# ProPrj__2_2025-03-13.net
KiCad netlist of a schematic drawn in EasyEDA Pro
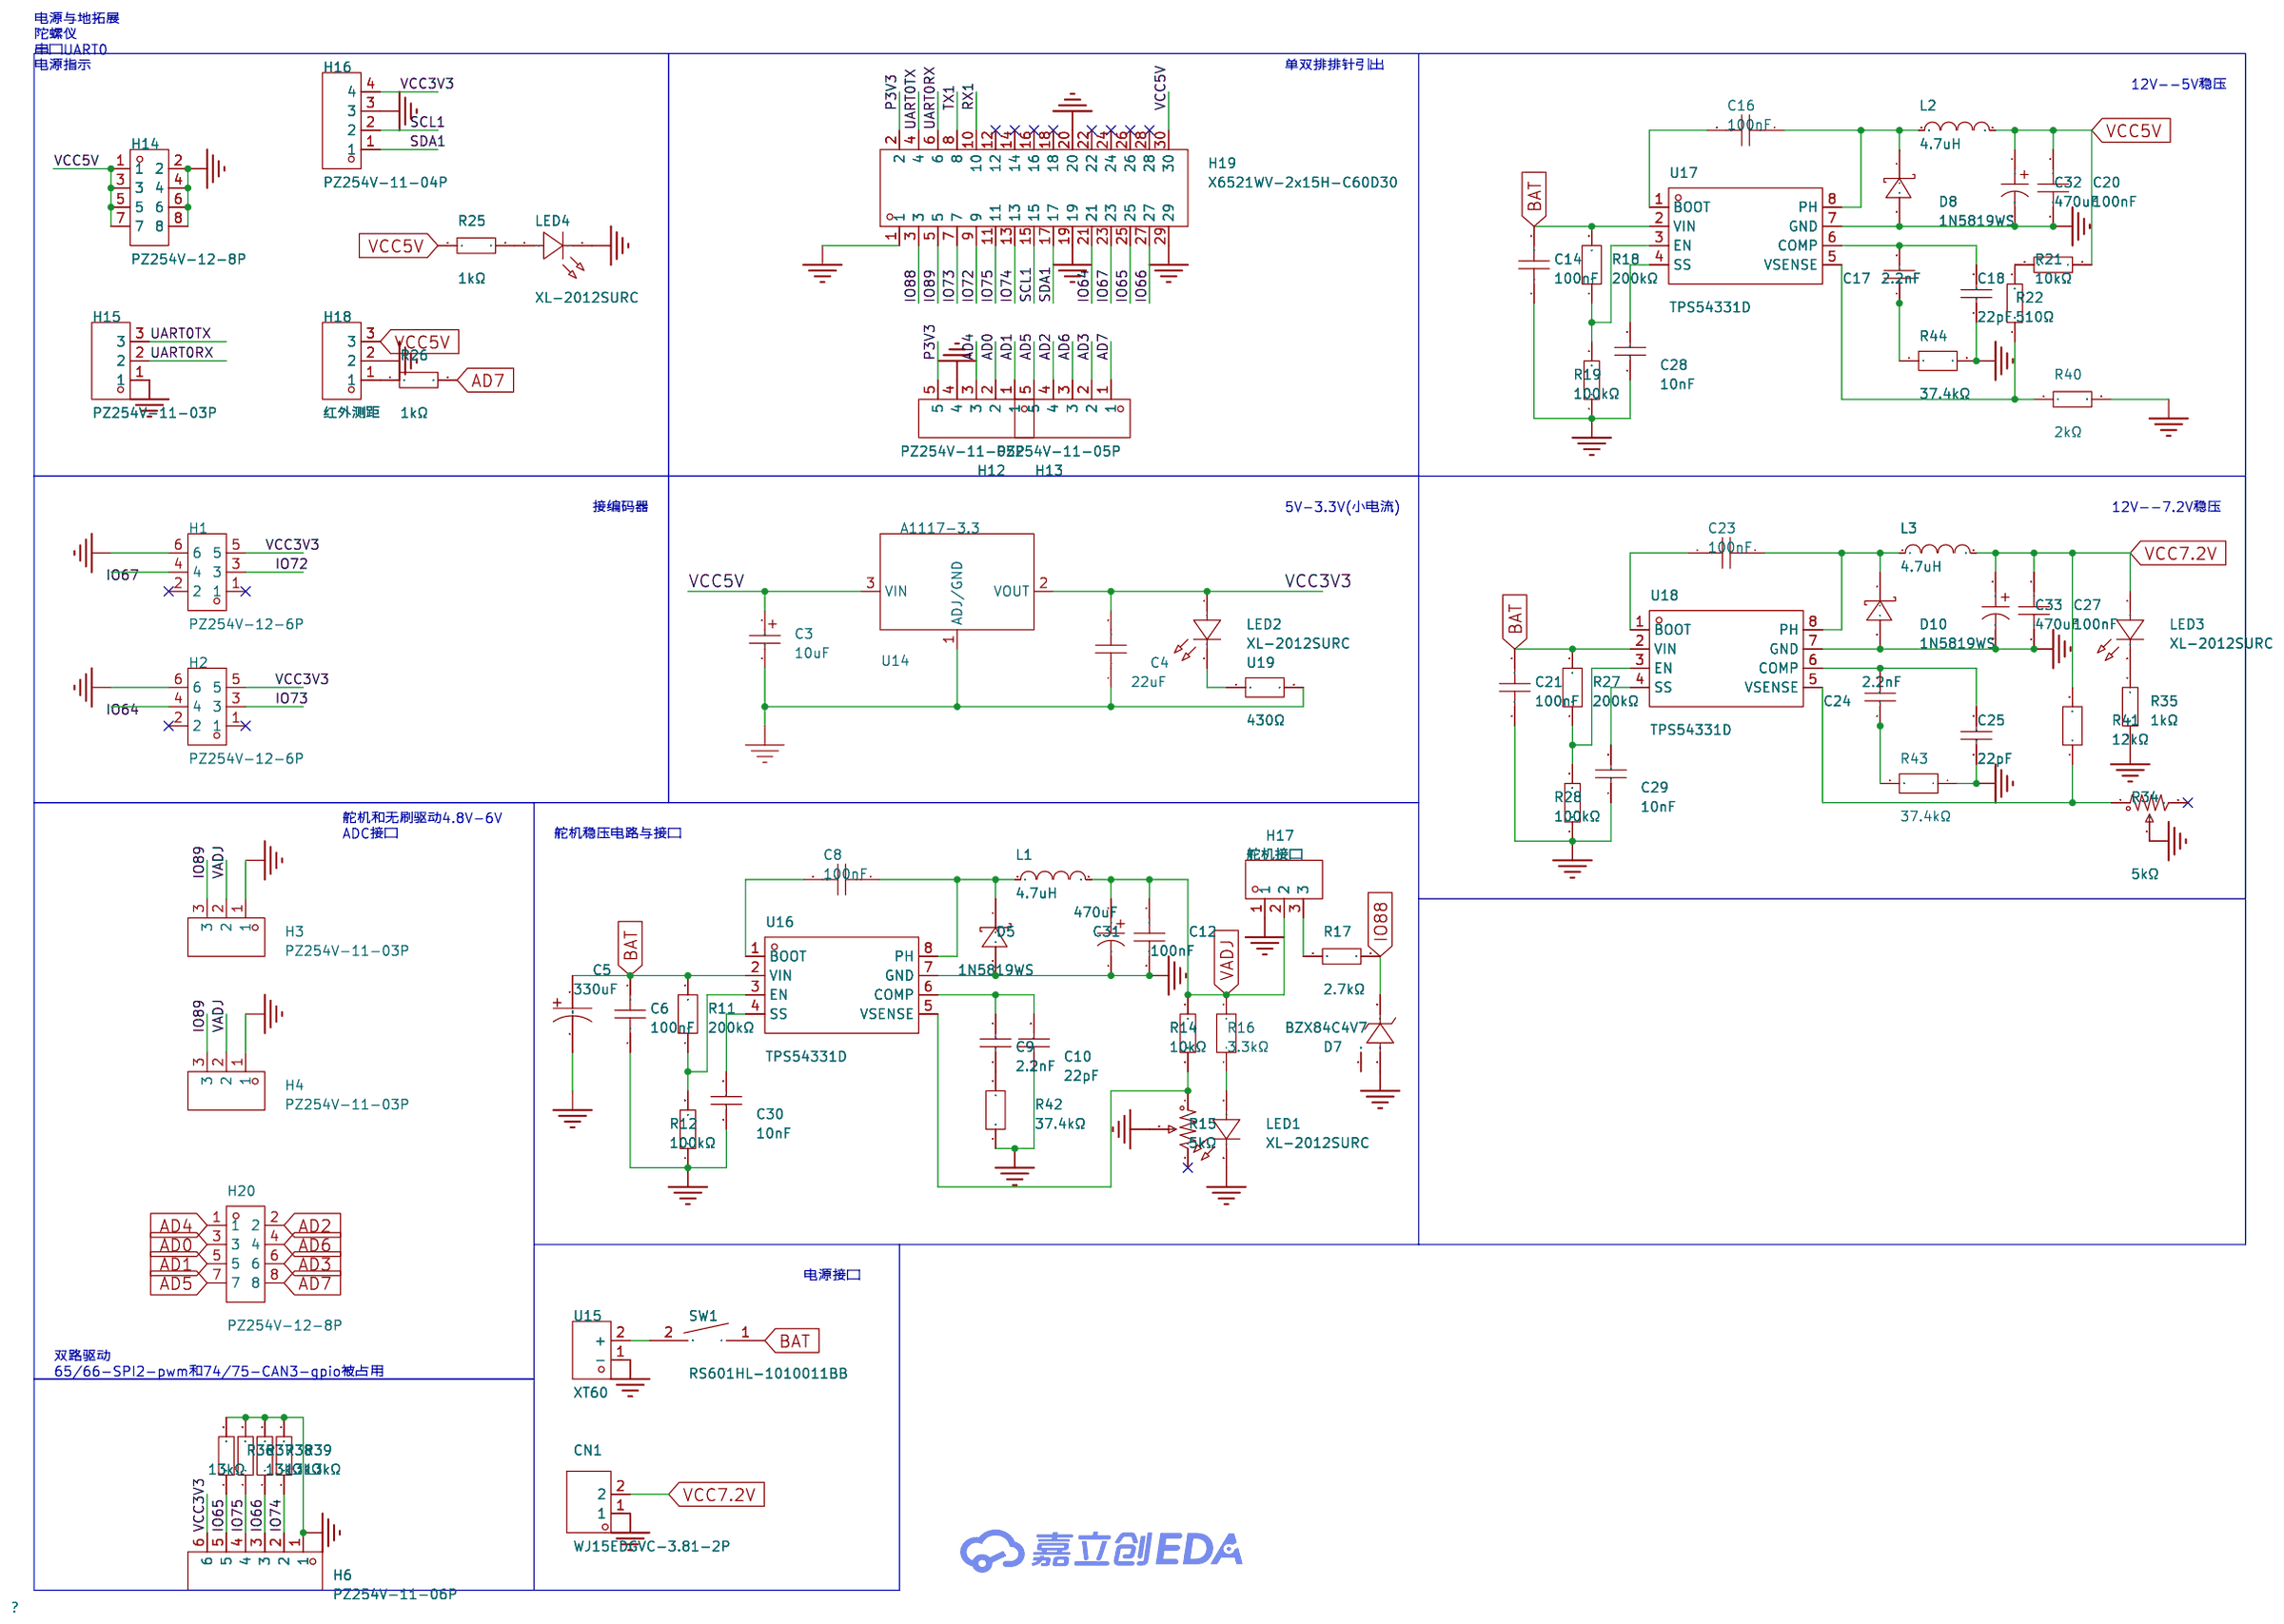
[diagram p0: schematic sheet]

(export (version "E")
  (design (tool "Eeschema 10.0.6"))
  (components
    (comp (ref "C3")
      (value "10uF")
      (footprint "easyedapro:CAP-SMD_L6.0-W3.2")
      (description "容值:10uF;精度:±10%;额定电压:16V;等效串联电阻:2Ω@100kHz;")
      (fields (field (name "Manufacturer Part") "TAJC106K016RNJ") (field (name "Manufacturer") "Kyocera AVX"))
      (libsource (lib "easyedapro") (part "TAJC106K016RNJ"))
    )
    (comp (ref "C4")
      (value "22uF")
      (footprint "easyedapro:C0805")
      (description "容值:22uF;精度:±20%;额定电压:35V;材质(温度系数):X5R;")
      (fields
        (field (name "Manufacturer Part") "CGA0805X5R226M350MT")
        (field (name "Manufacturer") "HRE(芯声)")
      )
      (libsource (lib "easyedapro") (part "CGA0805X5R226M350MT"))
    )
    (comp (ref "C5")
      (value "330uF")
      (footprint "easyedapro:CAP-SMD_BD8.0-L8.3-W8.3-LS9.3-FD-1")
      (description "容值:330uF;精度:±20%;额定电压:25V;纹波电流:228mA@120Hz;等效串联电阻(ESR):-;")
      (fields (field (name "Manufacturer Part") "RVT1E331M0810") (field (name "Manufacturer") "ROQANG(容强)"))
      (libsource (lib "easyedapro") (part "RVT1E331M0810_C335985"))
    )
    (comp (ref "C6")
      (value "100nF")
      (footprint "easyedapro:C0805")
      (description "容值:100nF;精度:±10%;额定电压:50V;材质(温度系数):X7R;")
      (fields
        (field (name "Manufacturer Part") "CC0805KRX7R9BB104")
        (field (name "Manufacturer") "YAGEO(国巨)")
      )
      (libsource (lib "easyedapro") (part "CC0805KRX7R9BB104"))
    )
    (comp (ref "C8")
      (value "100nF")
      (footprint "easyedapro:C0805")
      (description "容值:100nF;精度:±10%;额定电压:50V;材质(温度系数):X7R;")
      (fields
        (field (name "Manufacturer Part") "CC0805KRX7R9BB104")
        (field (name "Manufacturer") "YAGEO(国巨)")
      )
      (libsource (lib "easyedapro") (part "CC0805KRX7R9BB104"))
    )
    (comp (ref "C9")
      (value "2.2nF")
      (footprint "easyedapro:C0805")
      (description "容值:2.2nF;精度:±5%;额定电压:50V;材质(温度系数):C0G;")
      (fields
        (field (name "Manufacturer Part") "CL21C222JBFNNNE")
        (field (name "Manufacturer") "SAMSUNG(三星)")
      )
      (libsource (lib "easyedapro") (part "CL21C222JBFNNNE"))
    )
    (comp (ref "C10")
      (value "22pF")
      (footprint "easyedapro:C0603")
      (description "容值:22pF;精度:±5%;额定电压:50V;材质(温度系数):NP0;")
      (fields
        (field (name "Manufacturer Part") "CC0603JRNPO9BN220")
        (field (name "Manufacturer") "YAGEO(国巨)")
      )
      (libsource (lib "easyedapro") (part "CC0603JRNPO9BN220"))
    )
    (comp (ref "C12")
      (value "100nF")
      (footprint "easyedapro:C0805")
      (description "容值:100nF;精度:±10%;额定电压:50V;材质(温度系数):X7R;")
      (fields
        (field (name "Manufacturer Part") "CC0805KRX7R9BB104")
        (field (name "Manufacturer") "YAGEO(国巨)")
      )
      (libsource (lib "easyedapro") (part "CC0805KRX7R9BB104"))
    )
    (comp (ref "C14")
      (value "100nF")
      (footprint "easyedapro:C0805")
      (description "容值:100nF;精度:±10%;额定电压:50V;材质(温度系数):X7R;")
      (fields
        (field (name "Manufacturer Part") "CC0805KRX7R9BB104")
        (field (name "Manufacturer") "YAGEO(国巨)")
      )
      (libsource (lib "easyedapro") (part "CC0805KRX7R9BB104"))
    )
    (comp (ref "C16")
      (value "100nF")
      (footprint "easyedapro:C0805")
      (description "容值:100nF;精度:±10%;额定电压:50V;材质(温度系数):X7R;")
      (fields
        (field (name "Manufacturer Part") "CC0805KRX7R9BB104")
        (field (name "Manufacturer") "YAGEO(国巨)")
      )
      (libsource (lib "easyedapro") (part "CC0805KRX7R9BB104"))
    )
    (comp (ref "C17")
      (value "2.2nF")
      (footprint "easyedapro:C0805")
      (description "容值:2.2nF;精度:±5%;额定电压:50V;材质(温度系数):C0G;")
      (fields
        (field (name "Manufacturer Part") "CL21C222JBFNNNE")
        (field (name "Manufacturer") "SAMSUNG(三星)")
      )
      (libsource (lib "easyedapro") (part "CL21C222JBFNNNE"))
    )
    (comp (ref "C18")
      (value "22pF")
      (footprint "easyedapro:C0603")
      (description "容值:22pF;精度:±5%;额定电压:50V;材质(温度系数):NP0;")
      (fields
        (field (name "Manufacturer Part") "CC0603JRNPO9BN220")
        (field (name "Manufacturer") "YAGEO(国巨)")
      )
      (libsource (lib "easyedapro") (part "CC0603JRNPO9BN220"))
    )
    (comp (ref "C20")
      (value "100nF")
      (footprint "easyedapro:C0805")
      (description "容值:100nF;精度:±10%;额定电压:50V;材质(温度系数):X7R;")
      (fields
        (field (name "Manufacturer Part") "CC0805KRX7R9BB104")
        (field (name "Manufacturer") "YAGEO(国巨)")
      )
      (libsource (lib "easyedapro") (part "CC0805KRX7R9BB104"))
    )
    (comp (ref "C21")
      (value "100nF")
      (footprint "easyedapro:C0805")
      (description "容值:100nF;精度:±10%;额定电压:50V;材质(温度系数):X7R;")
      (fields
        (field (name "Manufacturer Part") "CC0805KRX7R9BB104")
        (field (name "Manufacturer") "YAGEO(国巨)")
      )
      (libsource (lib "easyedapro") (part "CC0805KRX7R9BB104"))
    )
    (comp (ref "C23")
      (value "100nF")
      (footprint "easyedapro:C0805")
      (description "容值:100nF;精度:±10%;额定电压:50V;材质(温度系数):X7R;")
      (fields
        (field (name "Manufacturer Part") "CC0805KRX7R9BB104")
        (field (name "Manufacturer") "YAGEO(国巨)")
      )
      (libsource (lib "easyedapro") (part "CC0805KRX7R9BB104"))
    )
    (comp (ref "C24")
      (value "2.2nF")
      (footprint "easyedapro:C0805")
      (description "容值:2.2nF;精度:±5%;额定电压:50V;材质(温度系数):C0G;")
      (fields
        (field (name "Manufacturer Part") "CL21C222JBFNNNE")
        (field (name "Manufacturer") "SAMSUNG(三星)")
      )
      (libsource (lib "easyedapro") (part "CL21C222JBFNNNE"))
    )
    (comp (ref "C25")
      (value "22pF")
      (footprint "easyedapro:C0603")
      (description "容值:22pF;精度:±5%;额定电压:50V;材质(温度系数):NP0;")
      (fields
        (field (name "Manufacturer Part") "CC0603JRNPO9BN220")
        (field (name "Manufacturer") "YAGEO(国巨)")
      )
      (libsource (lib "easyedapro") (part "CC0603JRNPO9BN220"))
    )
    (comp (ref "C27")
      (value "100nF")
      (footprint "easyedapro:C0805")
      (description "容值:100nF;精度:±10%;额定电压:50V;材质(温度系数):X7R;")
      (fields
        (field (name "Manufacturer Part") "CC0805KRX7R9BB104")
        (field (name "Manufacturer") "YAGEO(国巨)")
      )
      (libsource (lib "easyedapro") (part "CC0805KRX7R9BB104"))
    )
    (comp (ref "C28")
      (value "10nF")
      (footprint "easyedapro:C0805")
      (description "容值:10nF;精度:±10%;额定电压:50V;材质(温度系数):X7R;")
      (fields
        (field (name "Manufacturer Part") "CL21B103KBANNNC")
        (field (name "Manufacturer") "SAMSUNG(三星)")
      )
      (libsource (lib "easyedapro") (part "CL21B103KBANNNC"))
    )
    (comp (ref "C29")
      (value "10nF")
      (footprint "easyedapro:C0805")
      (description "容值:10nF;精度:±10%;额定电压:50V;材质(温度系数):X7R;")
      (fields
        (field (name "Manufacturer Part") "CL21B103KBANNNC")
        (field (name "Manufacturer") "SAMSUNG(三星)")
      )
      (libsource (lib "easyedapro") (part "CL21B103KBANNNC"))
    )
    (comp (ref "C30")
      (value "10nF")
      (footprint "easyedapro:C0805")
      (description "容值:10nF;精度:±10%;额定电压:50V;材质(温度系数):X7R;")
      (fields
        (field (name "Manufacturer Part") "CL21B103KBANNNC")
        (field (name "Manufacturer") "SAMSUNG(三星)")
      )
      (libsource (lib "easyedapro") (part "CL21B103KBANNNC"))
    )
    (comp (ref "C31")
      (value "470uF")
      (footprint "easyedapro:CAP-SMD_BD8.0-L8.3-W8.3-LS8.9-FD")
      (description "容值:470uF;精度:±20%;额定电压:16V;纹波电流:240mA@120Hz;")
      (fields (field (name "Manufacturer Part") "CK1C471M-CRF10") (field (name "Manufacturer") "ROQANG(容强)"))
      (libsource (lib "easyedapro") (part "CK1C471M-CRF10_C5162359"))
    )
    (comp (ref "C32")
      (value "470uF")
      (footprint "easyedapro:CAP-SMD_BD8.0-L8.3-W8.3-LS8.9-FD")
      (description "容值:470uF;精度:±20%;额定电压:16V;纹波电流:240mA@120Hz;")
      (fields (field (name "Manufacturer Part") "CK1C471M-CRF10") (field (name "Manufacturer") "ROQANG(容强)"))
      (libsource (lib "easyedapro") (part "CK1C471M-CRF10_C5162359"))
    )
    (comp (ref "C33")
      (value "470uF")
      (footprint "easyedapro:CAP-SMD_BD8.0-L8.3-W8.3-LS8.9-FD")
      (description "容值:470uF;精度:±20%;额定电压:16V;纹波电流:240mA@120Hz;")
      (fields (field (name "Manufacturer Part") "CK1C471M-CRF10") (field (name "Manufacturer") "ROQANG(容强)"))
      (libsource (lib "easyedapro") (part "CK1C471M-CRF10_C5162359"))
    )
    (comp (ref "CN1")
      (value "WJ15EDGVC-3.81-2P")
      (footprint "easyedapro:CONN-TH_WJ15EDGVC-3.81-2P")
      (fields (field (name "Manufacturer") "KANGNEX(康奈克斯电气)"))
      (libsource (lib "easyedapro") (part "WJ15EDGVC-3.81-2P"))
    )
    (comp (ref "D5")
      (value "1N5819WS")
      (footprint "easyedapro:SOD-323_L1.8-W1.3-LS2.5-RD")
      (description "正向压降(Vf):600mV@1A;直流反向耐压(Vr):40V;整流电流:1A;")
      (fields (field (name "Manufacturer") "Hottech(合科泰)"))
      (libsource (lib "easyedapro") (part "1N5819WS"))
    )
    (comp (ref "D7")
      (value "BZX84C4V7")
      (footprint "easyedapro:SOT-23-3_L2.9-W1.3-P1.90-LS2.4-BR")
      (description "二极管配置:独立式;稳压值(标称值):4.7V;稳压值(范围):4.4V~5V;耗散功率(Pd):350mW;")
      (fields (field (name "Manufacturer") "LGE(鲁光)"))
      (libsource (lib "easyedapro") (part "BZX84C4V7_C841158"))
    )
    (comp (ref "D8")
      (value "1N5819WS")
      (footprint "easyedapro:SOD-323_L1.8-W1.3-LS2.5-RD")
      (description "正向压降(Vf):600mV@1A;直流反向耐压(Vr):40V;整流电流:1A;")
      (fields (field (name "Manufacturer") "Hottech(合科泰)"))
      (libsource (lib "easyedapro") (part "1N5819WS"))
    )
    (comp (ref "D10")
      (value "1N5819WS")
      (footprint "easyedapro:SOD-323_L1.8-W1.3-LS2.5-RD")
      (description "正向压降(Vf):600mV@1A;直流反向耐压(Vr):40V;整流电流:1A;")
      (fields (field (name "Manufacturer") "Hottech(合科泰)"))
      (libsource (lib "easyedapro") (part "1N5819WS"))
    )
    (comp (ref "H1")
      (value "PZ254V-12-6P")
      (footprint "easyedapro:HDR-TH_6P-P2.54-V-M-R2-C3-S2.54")
      (fields (field (name "Manufacturer") "XFCN(兴飞)"))
      (libsource (lib "easyedapro") (part "PZ254V-12-6P"))
    )
    (comp (ref "H2")
      (value "PZ254V-12-6P")
      (footprint "easyedapro:HDR-TH_6P-P2.54-V-M-R2-C3-S2.54")
      (fields (field (name "Manufacturer") "XFCN(兴飞)"))
      (libsource (lib "easyedapro") (part "PZ254V-12-6P"))
    )
    (comp (ref "H3")
      (value "PZ254V-11-03P")
      (footprint "easyedapro:HDR-TH_3P-P2.54-V-M")
      (fields (field (name "Manufacturer") "XFCN(兴飞)"))
      (libsource (lib "easyedapro") (part "PZ254V-11-03P_C2937625"))
    )
    (comp (ref "H4")
      (value "PZ254V-11-03P")
      (footprint "easyedapro:HDR-TH_3P-P2.54-V-M")
      (fields (field (name "Manufacturer") "XFCN(兴飞)"))
      (libsource (lib "easyedapro") (part "PZ254V-11-03P_C2937625"))
    )
    (comp (ref "H6")
      (value "PZ254V-11-06P")
      (footprint "easyedapro:HDR-TH_6P-P2.54-V-M")
      (fields (field (name "Manufacturer") "XFCN(兴飞)"))
      (libsource (lib "easyedapro") (part "PZ254V-11-06P"))
    )
    (comp (ref "H12")
      (value "PZ254V-11-05P")
      (footprint "easyedapro:HDR-TH_5P-P2.54-V-M")
      (fields (field (name "Manufacturer") "XFCN(兴飞)"))
      (libsource (lib "easyedapro") (part "PZ254V-11-05P"))
    )
    (comp (ref "H13")
      (value "PZ254V-11-05P")
      (footprint "easyedapro:HDR-TH_5P-P2.54-V-M")
      (fields (field (name "Manufacturer") "XFCN(兴飞)"))
      (libsource (lib "easyedapro") (part "PZ254V-11-05P"))
    )
    (comp (ref "H14")
      (value "PZ254V-12-8P")
      (footprint "easyedapro:HDR-TH_8P-P2.54-V-M-R2-C4-S2.54")
      (fields (field (name "Manufacturer") "XFCN(兴飞)"))
      (libsource (lib "easyedapro") (part "PZ254V-12-8P"))
    )
    (comp (ref "H15")
      (value "PZ254V-11-03P")
      (footprint "easyedapro:HDR-TH_3P-P2.54-V-M")
      (fields (field (name "Manufacturer") "XFCN(兴飞)"))
      (libsource (lib "easyedapro") (part "PZ254V-11-03P_C2937625"))
    )
    (comp (ref "H16")
      (value "PZ254V-11-04P")
      (footprint "easyedapro:HDR-TH_4P-P2.54-V-M")
      (fields (field (name "Manufacturer") "XFCN(兴飞)"))
      (libsource (lib "easyedapro") (part "PZ254V-11-04P_C2691448"))
    )
    (comp (ref "H17")
      (value "舵机接口")
      (footprint "easyedapro:HDR-TH_3P-P2.54-V-M")
      (fields (field (name "Manufacturer") "XFCN(兴飞)"))
      (libsource (lib "easyedapro") (part "PZ254V-11-03P_C2937625"))
    )
    (comp (ref "H18")
      (value "红外测距")
      (footprint "easyedapro:HDR-TH_3P-P2.54-V-M")
      (fields (field (name "Manufacturer") "XFCN(兴飞)"))
      (libsource (lib "easyedapro") (part "PZ254V-11-03P_C2937625"))
    )
    (comp (ref "H19")
      (value "X6521WV-2x15H-C60D30")
      (footprint "easyedapro:HDR-TH_30P-P2.54-V-M-R2-C15-S2.54-BL")
      (fields (field (name "Manufacturer") "XKB Connection(中国星坤)"))
      (libsource (lib "easyedapro") (part "X6521WV-2×15H-C30D60"))
    )
    (comp (ref "H20")
      (value "PZ254V-12-8P")
      (footprint "easyedapro:HDR-TH_8P-P2.54-V-M-R2-C4-S2.54")
      (fields (field (name "Manufacturer") "XFCN(兴飞)"))
      (libsource (lib "easyedapro") (part "PZ254V-12-8P"))
    )
    (comp (ref "L1")
      (value "4.7uH")
      (footprint "easyedapro:IND-SMD_L7.3-W6.6_MHCI06030")
      (description "电感值:4.7uH;精度:±20%;额定电流:5.5A;")
      (fields
        (field (name "Manufacturer Part") "SLO0630H4R7MTT")
        (field (name "Manufacturer") "Sunltech(韩国顺磁)")
      )
      (libsource (lib "easyedapro") (part "SLO0630H4R7MTT"))
    )
    (comp (ref "L2")
      (value "4.7uH")
      (footprint "easyedapro:IND-SMD_L7.3-W6.6_MHCI06030")
      (description "电感值:4.7uH;精度:±20%;额定电流:5.5A;")
      (fields
        (field (name "Manufacturer Part") "SLO0630H4R7MTT")
        (field (name "Manufacturer") "Sunltech(韩国顺磁)")
      )
      (libsource (lib "easyedapro") (part "SLO0630H4R7MTT"))
    )
    (comp (ref "L3")
      (value "4.7uH")
      (footprint "easyedapro:IND-SMD_L7.3-W6.6_MHCI06030")
      (description "电感值:4.7uH;精度:±20%;额定电流:5.5A;")
      (fields
        (field (name "Manufacturer Part") "SLO0630H4R7MTT")
        (field (name "Manufacturer") "Sunltech(韩国顺磁)")
      )
      (libsource (lib "easyedapro") (part "SLO0630H4R7MTT"))
    )
    (comp (ref "LED1")
      (value "XL-2012SURC")
      (footprint "easyedapro:LED0805-R-RD")
      (description "发光颜色:红色;功率:55mW;正向电流:25mA;主波长:617nm~621nm;透镜颜色:无色透明透镜;色温:-;发光角度:120°;载带方式:正贴;工作温度:-30°C~+85°C;")
      (fields (field (name "Manufacturer") "XINGLIGHT(成兴光)"))
      (libsource (lib "easyedapro") (part "XL-2012SURC"))
    )
    (comp (ref "LED2")
      (value "XL-2012SURC")
      (footprint "easyedapro:LED0805-R-RD")
      (description "发光颜色:红色;功率:55mW;正向电流:25mA;主波长:617nm~621nm;透镜颜色:无色透明透镜;色温:-;发光角度:120°;载带方式:正贴;工作温度:-30°C~+85°C;")
      (fields (field (name "Manufacturer") "XINGLIGHT(成兴光)"))
      (libsource (lib "easyedapro") (part "XL-2012SURC"))
    )
    (comp (ref "LED3")
      (value "XL-2012SURC")
      (footprint "easyedapro:LED0805-R-RD")
      (description "发光颜色:红色;功率:55mW;正向电流:25mA;主波长:617nm~621nm;透镜颜色:无色透明透镜;色温:-;发光角度:120°;载带方式:正贴;工作温度:-30°C~+85°C;")
      (fields (field (name "Manufacturer") "XINGLIGHT(成兴光)"))
      (libsource (lib "easyedapro") (part "XL-2012SURC"))
    )
    (comp (ref "LED4")
      (value "XL-2012SURC")
      (footprint "easyedapro:LED0805-R-RD")
      (description "发光颜色:红色;功率:55mW;正向电流:25mA;主波长:617nm~621nm;透镜颜色:无色透明透镜;色温:-;发光角度:120°;载带方式:正贴;工作温度:-30°C~+85°C;")
      (fields (field (name "Manufacturer") "XINGLIGHT(成兴光)"))
      (libsource (lib "easyedapro") (part "XL-2012SURC"))
    )
    (comp (ref "R11")
      (value "200kΩ")
      (footprint "easyedapro:R0603")
      (description "电阻类型:厚膜电阻;阻值:200kΩ;精度:±1%;功率:100mW;工作电压:75V;温度系数:±100ppm/°C;")
      (fields (field (name "Manufacturer Part") "FRC0603F2003TS") (field (name "Manufacturer") "FOJAN(富捷)"))
      (libsource (lib "easyedapro") (part "FRC0603F2003TS"))
    )
    (comp (ref "R12")
      (value "100kΩ")
      (footprint "easyedapro:R0805")
      (description "电阻类型:厚膜电阻;阻值:100kΩ;精度:±1%;功率:125mW;最大工作电压:150V;温度系数:±100ppm/°C;")
      (fields
        (field (name "Manufacturer Part") "0805W8F1003T5E")
        (field (name "Manufacturer") "UNI-ROYAL(厚声)")
      )
      (libsource (lib "easyedapro") (part "0805W8F1003T5E_C149504"))
    )
    (comp (ref "R14")
      (value "10kΩ")
      (footprint "easyedapro:R0805")
      (description "电阻类型:厚膜电阻;阻值:10kΩ;精度:±1%;功率:125mW;最大工作电压:150V;温度系数:±100ppm/°C;")
      (fields
        (field (name "Manufacturer Part") "0805W8F1002T5E")
        (field (name "Manufacturer") "UNI-ROYAL(厚声)")
      )
      (libsource (lib "easyedapro") (part "0805W8F1002T5E"))
    )
    (comp (ref "R15")
      (value "5kΩ")
      (footprint "easyedapro:RES-ADJ-TH_3P-L6.8-W4.6-P2.50-TL-BS-3266X")
      (description "阻值:5kΩ;精度:±10%;功率:250mW;温度系数:±100ppm/°C;")
      (fields (field (name "Manufacturer Part") "3266X-1-502LF") (field (name "Manufacturer") "BOURNS"))
      (libsource (lib "easyedapro") (part "3266X-1-502LF"))
    )
    (comp (ref "R16")
      (value "3.3kΩ")
      (footprint "easyedapro:R0805")
      (description "电阻类型:厚膜电阻;阻值:3.3kΩ;精度:±1%;功率:125mW;最大工作电压:150V;温度系数:±100ppm/°C;")
      (fields (field (name "Manufacturer Part") "FRC0805F3301TS") (field (name "Manufacturer") "FOJAN(富捷)"))
      (libsource (lib "easyedapro") (part "FRC0805F3301TS"))
    )
    (comp (ref "R17")
      (value "2.7kΩ")
      (footprint "easyedapro:R0603")
      (description "电阻类型:厚膜电阻;阻值:2.7kΩ;精度:±1%;功率:100mW;最大工作电压:75V;温度系数:±100ppm/°C;")
      (fields
        (field (name "Manufacturer Part") "0603WAF2701T5E")
        (field (name "Manufacturer") "UNI-ROYAL(厚声)")
      )
      (libsource (lib "easyedapro") (part "0603WAF2701T5E"))
    )
    (comp (ref "R18")
      (value "200kΩ")
      (footprint "easyedapro:R0603")
      (description "电阻类型:厚膜电阻;阻值:200kΩ;精度:±1%;功率:100mW;工作电压:75V;温度系数:±100ppm/°C;")
      (fields (field (name "Manufacturer Part") "FRC0603F2003TS") (field (name "Manufacturer") "FOJAN(富捷)"))
      (libsource (lib "easyedapro") (part "FRC0603F2003TS"))
    )
    (comp (ref "R19")
      (value "100kΩ")
      (footprint "easyedapro:R0805")
      (description "电阻类型:厚膜电阻;阻值:100kΩ;精度:±1%;功率:125mW;最大工作电压:150V;温度系数:±100ppm/°C;")
      (fields
        (field (name "Manufacturer Part") "0805W8F1003T5E")
        (field (name "Manufacturer") "UNI-ROYAL(厚声)")
      )
      (libsource (lib "easyedapro") (part "0805W8F1003T5E_C149504"))
    )
    (comp (ref "R21")
      (value "10kΩ")
      (footprint "easyedapro:R0805")
      (description "电阻类型:厚膜电阻;阻值:10kΩ;精度:±1%;功率:125mW;最大工作电压:150V;温度系数:±100ppm/°C;")
      (fields
        (field (name "Manufacturer Part") "0805W8F1002T5E")
        (field (name "Manufacturer") "UNI-ROYAL(厚声)")
      )
      (libsource (lib "easyedapro") (part "0805W8F1002T5E"))
    )
    (comp (ref "R22")
      (value "510Ω")
      (footprint "easyedapro:R0603")
      (description "电阻类型:厚膜电阻;阻值:510Ω;精度:±1%;功率:100mW;最大工作电压:75V;温度系数:±100ppm/°C;")
      (fields
        (field (name "Manufacturer Part") "0603WAF5100T5E")
        (field (name "Manufacturer") "UNI-ROYAL(厚声)")
      )
      (libsource (lib "easyedapro") (part "0603WAF5100T5E"))
    )
    (comp (ref "R25")
      (value "1kΩ")
      (footprint "easyedapro:R0603")
      (description "电阻类型:厚膜电阻;阻值:1kΩ;精度:±1%;功率:100mW;最大工作电压:75V;温度系数:±100ppm/°C;")
      (fields
        (field (name "Manufacturer Part") "0603WAF1001T5E")
        (field (name "Manufacturer") "UNI-ROYAL(厚声)")
      )
      (libsource (lib "easyedapro") (part "0603WAF1001T5E"))
    )
    (comp (ref "R26")
      (value "1kΩ")
      (footprint "easyedapro:R0603")
      (description "电阻类型:厚膜电阻;阻值:1kΩ;精度:±1%;功率:100mW;最大工作电压:75V;温度系数:±100ppm/°C;")
      (fields
        (field (name "Manufacturer Part") "0603WAF1001T5E")
        (field (name "Manufacturer") "UNI-ROYAL(厚声)")
      )
      (libsource (lib "easyedapro") (part "0603WAF1001T5E"))
    )
    (comp (ref "R27")
      (value "200kΩ")
      (footprint "easyedapro:R0603")
      (description "电阻类型:厚膜电阻;阻值:200kΩ;精度:±1%;功率:100mW;工作电压:75V;温度系数:±100ppm/°C;")
      (fields (field (name "Manufacturer Part") "FRC0603F2003TS") (field (name "Manufacturer") "FOJAN(富捷)"))
      (libsource (lib "easyedapro") (part "FRC0603F2003TS"))
    )
    (comp (ref "R28")
      (value "100kΩ")
      (footprint "easyedapro:R0805")
      (description "电阻类型:厚膜电阻;阻值:100kΩ;精度:±1%;功率:125mW;最大工作电压:150V;温度系数:±100ppm/°C;")
      (fields
        (field (name "Manufacturer Part") "0805W8F1003T5E")
        (field (name "Manufacturer") "UNI-ROYAL(厚声)")
      )
      (libsource (lib "easyedapro") (part "0805W8F1003T5E_C149504"))
    )
    (comp (ref "R34")
      (value "5kΩ")
      (footprint "easyedapro:RES-ADJ-TH_3P-L6.8-W4.6-P2.50-TL-BS-3266X")
      (description "阻值:5kΩ;精度:±10%;功率:250mW;温度系数:±100ppm/°C;")
      (fields (field (name "Manufacturer Part") "3266X-1-502LF") (field (name "Manufacturer") "BOURNS"))
      (libsource (lib "easyedapro") (part "3266X-1-502LF"))
    )
    (comp (ref "R35")
      (value "1kΩ")
      (footprint "easyedapro:R0603")
      (description "电阻类型:厚膜电阻;阻值:510Ω;精度:±1%;功率:100mW;最大工作电压:75V;温度系数:±100ppm/°C;")
      (fields
        (field (name "Manufacturer Part") "0603WAF5100T5E")
        (field (name "Manufacturer") "UNI-ROYAL(厚声)")
      )
      (libsource (lib "easyedapro") (part "0603WAF5100T5E"))
    )
    (comp (ref "R36")
      (value "13kΩ")
      (footprint "easyedapro:R0805")
      (description "电阻类型:厚膜电阻;阻值:13kΩ;精度:±1%;功率:125mW;最大工作电压:150V;温度系数:±100ppm/°C;")
      (fields
        (field (name "Manufacturer Part") "0805W8F1302T5E")
        (field (name "Manufacturer") "UNI-ROYAL(厚声)")
      )
      (libsource (lib "easyedapro") (part "0805W8F1302T5E"))
    )
    (comp (ref "R37")
      (value "13kΩ")
      (footprint "easyedapro:R0805")
      (description "电阻类型:厚膜电阻;阻值:13kΩ;精度:±1%;功率:125mW;最大工作电压:150V;温度系数:±100ppm/°C;")
      (fields
        (field (name "Manufacturer Part") "0805W8F1302T5E")
        (field (name "Manufacturer") "UNI-ROYAL(厚声)")
      )
      (libsource (lib "easyedapro") (part "0805W8F1302T5E"))
    )
    (comp (ref "R38")
      (value "13kΩ")
      (footprint "easyedapro:R0805")
      (description "电阻类型:厚膜电阻;阻值:13kΩ;精度:±1%;功率:125mW;最大工作电压:150V;温度系数:±100ppm/°C;")
      (fields
        (field (name "Manufacturer Part") "0805W8F1302T5E")
        (field (name "Manufacturer") "UNI-ROYAL(厚声)")
      )
      (libsource (lib "easyedapro") (part "0805W8F1302T5E"))
    )
    (comp (ref "R39")
      (value "13kΩ")
      (footprint "easyedapro:R0805")
      (description "电阻类型:厚膜电阻;阻值:13kΩ;精度:±1%;功率:125mW;最大工作电压:150V;温度系数:±100ppm/°C;")
      (fields
        (field (name "Manufacturer Part") "0805W8F1302T5E")
        (field (name "Manufacturer") "UNI-ROYAL(厚声)")
      )
      (libsource (lib "easyedapro") (part "0805W8F1302T5E"))
    )
    (comp (ref "R40")
      (value "2kΩ")
      (footprint "easyedapro:R0805")
      (description "电阻类型:厚膜电阻;阻值:2kΩ;精度:±1%;功率:125mW;最大工作电压:150V;温度系数:±100ppm/°C;")
      (fields
        (field (name "Manufacturer Part") "0805W8F2001T5E")
        (field (name "Manufacturer") "UNI-ROYAL(厚声)")
      )
      (libsource (lib "easyedapro") (part "0805W8F2001T5E"))
    )
    (comp (ref "R41")
      (value "12kΩ")
      (footprint "easyedapro:R0805")
      (description "电阻类型:厚膜电阻;阻值:12kΩ;精度:±1%;功率:125mW;最大工作电压:150V;温度系数:±100ppm/°C;")
      (fields (field (name "Manufacturer Part") "FRC0805F1202TS") (field (name "Manufacturer") "FOJAN(富捷)"))
      (libsource (lib "easyedapro") (part "FRC0805F1202TS"))
    )
    (comp (ref "R42")
      (value "37.4kΩ")
      (footprint "easyedapro:R0603")
      (description "电阻类型:薄膜电阻;阻值:37kΩ;精度:±0.25%;功率:100mW;最大工作电压:75V;温度系数:±25ppm/°C;")
      (fields (field (name "Manufacturer Part") "RN73R1JTTD3702C25") (field (name "Manufacturer") "KOA"))
      (libsource (lib "easyedapro") (part "RN73R1JTTD3702C25"))
    )
    (comp (ref "R43")
      (value "37.4kΩ")
      (footprint "easyedapro:R0603")
      (description "电阻类型:薄膜电阻;阻值:37kΩ;精度:±0.25%;功率:100mW;最大工作电压:75V;温度系数:±25ppm/°C;")
      (fields (field (name "Manufacturer Part") "RN73R1JTTD3702C25") (field (name "Manufacturer") "KOA"))
      (libsource (lib "easyedapro") (part "RN73R1JTTD3702C25"))
    )
    (comp (ref "R44")
      (value "37.4kΩ")
      (footprint "easyedapro:R0603")
      (description "电阻类型:薄膜电阻;阻值:37kΩ;精度:±0.25%;功率:100mW;最大工作电压:75V;温度系数:±25ppm/°C;")
      (fields (field (name "Manufacturer Part") "RN73R1JTTD3702C25") (field (name "Manufacturer") "KOA"))
      (libsource (lib "easyedapro") (part "RN73R1JTTD3702C25"))
    )
    (comp (ref "SW1")
      (value "RS601HL-1010011BB")
      (footprint "easyedapro:SW-TH_RS601HL-1010011BB")
      (description "带灯:无;引脚样式:焊片;额定电流:3A;额定电压(AC):250V;额定电压(DC):-;电路结构:单刀单掷;机械寿命:1万次;")
      (fields (field (name "Manufacturer") "HCTL(华灿天禄)"))
      (libsource (lib "easyedapro") (part "RS601HL-1010011BB"))
    )
    (comp (ref "U14")
      (value "A1117-3.3")
      (footprint "easyedapro:asm1117")
      (fields (field (name "Manufacturer") "IDCHIP(英锐芯)"))
      (libsource (lib "easyedapro") (part "A1117-3.3"))
    )
    (comp (ref "U15")
      (value "XT60")
      (footprint "easyedapro:CONN-TH_XT60")
      (description "类别:-;类型1:-;")
      (fields (field (name "Manufacturer") "AMASS(艾迈斯)"))
      (libsource (lib "easyedapro") (part "XT60"))
    )
    (comp (ref "U16")
      (value "TPS54331D")
      (footprint "easyedapro:SOIC-8_L4.9-W3.9-P1.27-LS6.0-BL")
      (description "功能类型:降压型;输出类型:可调;输入电压:3.5V~28V;输出电压:-;输出电流:3A;")
      (fields (field (name "Manufacturer") "TI(德州仪器)"))
      (libsource (lib "easyedapro") (part "TPS54331D"))
    )
    (comp (ref "U17")
      (value "TPS54331D")
      (footprint "easyedapro:SOIC-8_L4.9-W3.9-P1.27-LS6.0-BL")
      (description "功能类型:降压型;输出类型:可调;输入电压:3.5V~28V;输出电压:-;输出电流:3A;")
      (fields (field (name "Manufacturer") "TI(德州仪器)"))
      (libsource (lib "easyedapro") (part "TPS54331D"))
    )
    (comp (ref "U18")
      (value "TPS54331D")
      (footprint "easyedapro:SOIC-8_L4.9-W3.9-P1.27-LS6.0-BL")
      (description "功能类型:降压型;输出类型:可调;输入电压:3.5V~28V;输出电压:-;输出电流:3A;")
      (fields (field (name "Manufacturer") "TI(德州仪器)"))
      (libsource (lib "easyedapro") (part "TPS54331D"))
    )
    (comp (ref "U19")
      (value "430Ω")
      (footprint "easyedapro:R0805")
      (description "电阻类型:厚膜电阻;阻值:430Ω;精度:±1%;功率:125mW;最大工作电压:150V;温度系数:±100ppm/°C;")
      (fields (field (name "Manufacturer Part") "FRC0805F4300TS") (field (name "Manufacturer") "FOJAN(富捷)"))
      (libsource (lib "easyedapro") (part "FRC0805F4300TS"))
    )
  )
  (nets
    (net (code "1") (name "/IO64") (class "Default")
      (node (ref "H19") (pin "21") (pinfunction "21_21") (pintype "unspecified"))
      (node (ref "H2") (pin "4") (pinfunction "4_4") (pintype "unspecified"))
    )
    (net (code "2") (name "/IO65") (class "Default")
      (node (ref "H19") (pin "25") (pinfunction "25_25") (pintype "unspecified"))
      (node (ref "H6") (pin "5") (pinfunction "5_5") (pintype "unspecified"))
      (node (ref "R36") (pin "1") (pinfunction "1_1") (pintype "input"))
    )
    (net (code "3") (name "/IO66") (class "Default")
      (node (ref "H19") (pin "27") (pinfunction "27_27") (pintype "unspecified"))
      (node (ref "H6") (pin "3") (pinfunction "3_3") (pintype "unspecified"))
      (node (ref "R38") (pin "1") (pinfunction "1_1") (pintype "input"))
    )
    (net (code "4") (name "/IO67") (class "Default")
      (node (ref "H1") (pin "4") (pinfunction "4_4") (pintype "unspecified"))
      (node (ref "H19") (pin "23") (pinfunction "23_23") (pintype "unspecified"))
    )
    (net (code "5") (name "/IO72") (class "Default")
      (node (ref "H1") (pin "3") (pinfunction "3_3") (pintype "unspecified"))
      (node (ref "H19") (pin "9") (pinfunction "9_9") (pintype "unspecified"))
    )
    (net (code "6") (name "/IO73") (class "Default")
      (node (ref "H19") (pin "7") (pinfunction "7_7") (pintype "unspecified"))
      (node (ref "H2") (pin "3") (pinfunction "3_3") (pintype "unspecified"))
    )
    (net (code "7") (name "/IO74") (class "Default")
      (node (ref "H19") (pin "13") (pinfunction "13_13") (pintype "unspecified"))
      (node (ref "H6") (pin "2") (pinfunction "2_2") (pintype "unspecified"))
      (node (ref "R39") (pin "1") (pinfunction "1_1") (pintype "input"))
    )
    (net (code "8") (name "/IO75") (class "Default")
      (node (ref "H19") (pin "11") (pinfunction "11_11") (pintype "unspecified"))
      (node (ref "H6") (pin "4") (pinfunction "4_4") (pintype "unspecified"))
      (node (ref "R37") (pin "1") (pinfunction "1_1") (pintype "input"))
    )
    (net (code "9") (name "/IO89") (class "Default")
      (node (ref "H19") (pin "5") (pinfunction "5_5") (pintype "unspecified"))
      (node (ref "H3") (pin "3") (pinfunction "3_3") (pintype "unspecified"))
      (node (ref "H4") (pin "3") (pinfunction "3_3") (pintype "unspecified"))
    )
    (net (code "10") (name "/P3V3") (class "Default")
      (node (ref "H12") (pin "5") (pinfunction "5_5") (pintype "unspecified"))
      (node (ref "H19") (pin "2") (pinfunction "2_2") (pintype "unspecified"))
    )
    (net (code "11") (name "/RX1") (class "Default")
      (node (ref "H19") (pin "10") (pinfunction "10_10") (pintype "unspecified"))
    )
    (net (code "12") (name "/SCL1") (class "Default")
      (node (ref "H16") (pin "2") (pinfunction "2_2") (pintype "unspecified"))
      (node (ref "H19") (pin "15") (pinfunction "15_15") (pintype "unspecified"))
    )
    (net (code "13") (name "/SDA1") (class "Default")
      (node (ref "H16") (pin "1") (pinfunction "1_1") (pintype "unspecified"))
      (node (ref "H19") (pin "17") (pinfunction "17_17") (pintype "unspecified"))
    )
    (net (code "14") (name "/TX1") (class "Default")
      (node (ref "H19") (pin "8") (pinfunction "8_8") (pintype "unspecified"))
    )
    (net (code "15") (name "/UART0RX") (class "Default")
      (node (ref "H15") (pin "2") (pinfunction "2_2") (pintype "unspecified"))
      (node (ref "H19") (pin "6") (pinfunction "6_6") (pintype "unspecified"))
    )
    (net (code "16") (name "/UART0TX") (class "Default")
      (node (ref "H15") (pin "3") (pinfunction "3_3") (pintype "unspecified"))
      (node (ref "H19") (pin "4") (pinfunction "4_4") (pintype "unspecified"))
    )
    (net (code "17") (name "/VCC3V3") (class "Default")
      (node (ref "C4") (pin "2") (pinfunction "2_2") (pintype "unspecified"))
      (node (ref "H1") (pin "5") (pinfunction "5_5") (pintype "unspecified"))
      (node (ref "H16") (pin "4") (pinfunction "4_4") (pintype "unspecified"))
      (node (ref "H2") (pin "5") (pinfunction "5_5") (pintype "unspecified"))
      (node (ref "H6") (pin "6") (pinfunction "6_6") (pintype "unspecified"))
      (node (ref "LED2") (pin "1") (pinfunction "A_1") (pintype "unspecified"))
      (node (ref "U14") (pin "2") (pinfunction "VOUT_2") (pintype "input"))
    )
    (net (code "18") (name "AD0") (class "Default")
      (node (ref "H12") (pin "2") (pinfunction "2_2") (pintype "unspecified"))
      (node (ref "H20") (pin "3") (pinfunction "3_3") (pintype "unspecified"))
    )
    (net (code "19") (name "AD1") (class "Default")
      (node (ref "H12") (pin "1") (pinfunction "1_1") (pintype "unspecified"))
      (node (ref "H20") (pin "5") (pinfunction "5_5") (pintype "unspecified"))
    )
    (net (code "20") (name "AD2") (class "Default")
      (node (ref "H13") (pin "4") (pinfunction "4_4") (pintype "unspecified"))
      (node (ref "H20") (pin "2") (pinfunction "2_2") (pintype "unspecified"))
    )
    (net (code "21") (name "AD3") (class "Default")
      (node (ref "H13") (pin "2") (pinfunction "2_2") (pintype "unspecified"))
      (node (ref "H20") (pin "6") (pinfunction "6_6") (pintype "unspecified"))
    )
    (net (code "22") (name "AD4") (class "Default")
      (node (ref "H12") (pin "3") (pinfunction "3_3") (pintype "unspecified"))
      (node (ref "H20") (pin "1") (pinfunction "1_1") (pintype "unspecified"))
    )
    (net (code "23") (name "AD5") (class "Default")
      (node (ref "H13") (pin "5") (pinfunction "5_5") (pintype "unspecified"))
      (node (ref "H20") (pin "7") (pinfunction "7_7") (pintype "unspecified"))
    )
    (net (code "24") (name "AD6") (class "Default")
      (node (ref "H13") (pin "3") (pinfunction "3_3") (pintype "unspecified"))
      (node (ref "H20") (pin "4") (pinfunction "4_4") (pintype "unspecified"))
    )
    (net (code "25") (name "AD7") (class "Default")
      (node (ref "H13") (pin "1") (pinfunction "1_1") (pintype "unspecified"))
      (node (ref "H20") (pin "8") (pinfunction "8_8") (pintype "unspecified"))
      (node (ref "R26") (pin "2") (pinfunction "2_2") (pintype "input"))
    )
    (net (code "26") (name "BAT") (class "Default")
      (node (ref "C14") (pin "2") (pinfunction "2_2") (pintype "unspecified"))
      (node (ref "C21") (pin "2") (pinfunction "2_2") (pintype "unspecified"))
      (node (ref "C5") (pin "1") (pinfunction "1_1") (pintype "unspecified"))
      (node (ref "C6") (pin "2") (pinfunction "2_2") (pintype "unspecified"))
      (node (ref "R11") (pin "2") (pinfunction "2_2") (pintype "unspecified"))
      (node (ref "R18") (pin "2") (pinfunction "2_2") (pintype "unspecified"))
      (node (ref "R27") (pin "2") (pinfunction "2_2") (pintype "unspecified"))
      (node (ref "SW1") (pin "1") (pinfunction "1_1") (pintype "input"))
      (node (ref "U16") (pin "2") (pinfunction "VIN_2") (pintype "unspecified"))
      (node (ref "U17") (pin "2") (pinfunction "VIN_2") (pintype "unspecified"))
      (node (ref "U18") (pin "2") (pinfunction "VIN_2") (pintype "unspecified"))
    )
    (net (code "27") (name "GND") (class "Default")
      (node (ref "C10") (pin "1") (pinfunction "1_1") (pintype "input"))
      (node (ref "C12") (pin "2") (pinfunction "2_2") (pintype "unspecified"))
      (node (ref "C14") (pin "1") (pinfunction "1_1") (pintype "unspecified"))
      (node (ref "C18") (pin "1") (pinfunction "1_1") (pintype "input"))
      (node (ref "C20") (pin "2") (pinfunction "2_2") (pintype "unspecified"))
      (node (ref "C21") (pin "1") (pinfunction "1_1") (pintype "unspecified"))
      (node (ref "C25") (pin "1") (pinfunction "1_1") (pintype "input"))
      (node (ref "C27") (pin "2") (pinfunction "2_2") (pintype "unspecified"))
      (node (ref "C28") (pin "1") (pinfunction "1_1") (pintype "input"))
      (node (ref "C29") (pin "1") (pinfunction "1_1") (pintype "input"))
      (node (ref "C3") (pin "2") (pinfunction "2_2") (pintype "input"))
      (node (ref "C30") (pin "1") (pinfunction "1_1") (pintype "input"))
      (node (ref "C31") (pin "2") (pinfunction "2_2") (pintype "input"))
      (node (ref "C32") (pin "2") (pinfunction "2_2") (pintype "input"))
      (node (ref "C33") (pin "2") (pinfunction "2_2") (pintype "input"))
      (node (ref "C4") (pin "1") (pinfunction "1_1") (pintype "unspecified"))
      (node (ref "C5") (pin "2") (pinfunction "2_2") (pintype "unspecified"))
      (node (ref "C6") (pin "1") (pinfunction "1_1") (pintype "unspecified"))
      (node (ref "CN1") (pin "1") (pinfunction "1_1") (pintype "unspecified"))
      (node (ref "D10") (pin "2") (pinfunction "A_2") (pintype "unspecified"))
      (node (ref "D5") (pin "2") (pinfunction "A_2") (pintype "unspecified"))
      (node (ref "D7") (pin "1") (pinfunction "A_1") (pintype "unspecified"))
      (node (ref "D8") (pin "2") (pinfunction "A_2") (pintype "unspecified"))
      (node (ref "H1") (pin "6") (pinfunction "6_6") (pintype "unspecified"))
      (node (ref "H12") (pin "4") (pinfunction "4_4") (pintype "unspecified"))
      (node (ref "H14") (pin "2") (pinfunction "2_2") (pintype "unspecified"))
      (node (ref "H14") (pin "4") (pinfunction "4_4") (pintype "unspecified"))
      (node (ref "H14") (pin "6") (pinfunction "6_6") (pintype "unspecified"))
      (node (ref "H14") (pin "8") (pinfunction "8_8") (pintype "unspecified"))
      (node (ref "H15") (pin "1") (pinfunction "1_1") (pintype "unspecified"))
      (node (ref "H16") (pin "3") (pinfunction "3_3") (pintype "unspecified"))
      (node (ref "H17") (pin "1") (pinfunction "1_1") (pintype "unspecified"))
      (node (ref "H18") (pin "2") (pinfunction "2_2") (pintype "unspecified"))
      (node (ref "H19") (pin "1") (pinfunction "1_1") (pintype "unspecified"))
      (node (ref "H19") (pin "19") (pinfunction "19_19") (pintype "unspecified"))
      (node (ref "H19") (pin "20") (pinfunction "20_20") (pintype "unspecified"))
      (node (ref "H19") (pin "29") (pinfunction "29_29") (pintype "unspecified"))
      (node (ref "H2") (pin "6") (pinfunction "6_6") (pintype "unspecified"))
      (node (ref "H3") (pin "1") (pinfunction "1_1") (pintype "unspecified"))
      (node (ref "H4") (pin "1") (pinfunction "1_1") (pintype "unspecified"))
      (node (ref "H6") (pin "1") (pinfunction "1_1") (pintype "unspecified"))
      (node (ref "LED1") (pin "2") (pinfunction "K_2") (pintype "unspecified"))
      (node (ref "LED4") (pin "2") (pinfunction "K_2") (pintype "unspecified"))
      (node (ref "R12") (pin "1") (pinfunction "1_1") (pintype "unspecified"))
      (node (ref "R15") (pin "2") (pinfunction "2_2") (pintype "unspecified"))
      (node (ref "R19") (pin "1") (pinfunction "1_1") (pintype "unspecified"))
      (node (ref "R28") (pin "1") (pinfunction "1_1") (pintype "unspecified"))
      (node (ref "R34") (pin "2") (pinfunction "2_2") (pintype "unspecified"))
      (node (ref "R35") (pin "2") (pinfunction "2_2") (pintype "input"))
      (node (ref "R36") (pin "2") (pinfunction "2_2") (pintype "input"))
      (node (ref "R37") (pin "2") (pinfunction "2_2") (pintype "input"))
      (node (ref "R38") (pin "2") (pinfunction "2_2") (pintype "input"))
      (node (ref "R39") (pin "2") (pinfunction "2_2") (pintype "input"))
      (node (ref "R40") (pin "2") (pinfunction "2_2") (pintype "input"))
      (node (ref "R42") (pin "1") (pinfunction "1_1") (pintype "unspecified"))
      (node (ref "R43") (pin "1") (pinfunction "1_1") (pintype "unspecified"))
      (node (ref "R44") (pin "2") (pinfunction "2_2") (pintype "unspecified"))
      (node (ref "U14") (pin "1") (pinfunction "ADJ/GND_1") (pintype "input"))
      (node (ref "U15") (pin "1") (pinfunction "-_1") (pintype "unspecified"))
      (node (ref "U16") (pin "7") (pinfunction "GND_7") (pintype "unspecified"))
      (node (ref "U17") (pin "7") (pinfunction "GND_7") (pintype "unspecified"))
      (node (ref "U18") (pin "7") (pinfunction "GND_7") (pintype "unspecified"))
      (node (ref "U19") (pin "2") (pinfunction "2_2") (pintype "unspecified"))
    )
    (net (code "28") (name "IO88") (class "Default")
      (node (ref "D7") (pin "3") (pinfunction "C_3") (pintype "unspecified"))
      (node (ref "H19") (pin "3") (pinfunction "3_3") (pintype "unspecified"))
      (node (ref "R17") (pin "1") (pinfunction "1_1") (pintype "input"))
    )
    (net (code "29") (name "Net-(C9-Pad1)") (class "Default")
      (node (ref "C9") (pin "1") (pinfunction "1_1") (pintype "input"))
      (node (ref "R42") (pin "2") (pinfunction "2_2") (pintype "unspecified"))
    )
    (net (code "30") (name "Net-(C17-Pad1)") (class "Default")
      (node (ref "C17") (pin "1") (pinfunction "1_1") (pintype "input"))
      (node (ref "R44") (pin "1") (pinfunction "1_1") (pintype "unspecified"))
    )
    (net (code "31") (name "Net-(C24-Pad1)") (class "Default")
      (node (ref "C24") (pin "1") (pinfunction "1_1") (pintype "input"))
      (node (ref "R43") (pin "2") (pinfunction "2_2") (pintype "unspecified"))
    )
    (net (code "32") (name "Net-(D5-K)") (class "Default")
      (node (ref "C8") (pin "1") (pinfunction "1_1") (pintype "unspecified"))
      (node (ref "D5") (pin "1") (pinfunction "K_1") (pintype "unspecified"))
      (node (ref "L1") (pin "1") (pinfunction "1_1") (pintype "unspecified"))
      (node (ref "U16") (pin "8") (pinfunction "PH_8") (pintype "unspecified"))
    )
    (net (code "33") (name "Net-(D8-K)") (class "Default")
      (node (ref "C16") (pin "1") (pinfunction "1_1") (pintype "unspecified"))
      (node (ref "D8") (pin "1") (pinfunction "K_1") (pintype "unspecified"))
      (node (ref "L2") (pin "1") (pinfunction "1_1") (pintype "unspecified"))
      (node (ref "U17") (pin "8") (pinfunction "PH_8") (pintype "unspecified"))
    )
    (net (code "34") (name "Net-(D10-K)") (class "Default")
      (node (ref "C23") (pin "1") (pinfunction "1_1") (pintype "unspecified"))
      (node (ref "D10") (pin "1") (pinfunction "K_1") (pintype "unspecified"))
      (node (ref "L3") (pin "1") (pinfunction "1_1") (pintype "unspecified"))
      (node (ref "U18") (pin "8") (pinfunction "PH_8") (pintype "unspecified"))
    )
    (net (code "35") (name "Net-(H17-Pad3)") (class "Default")
      (node (ref "H17") (pin "3") (pinfunction "3_3") (pintype "unspecified"))
      (node (ref "R17") (pin "2") (pinfunction "2_2") (pintype "input"))
    )
    (net (code "36") (name "Net-(H18-Pad1)") (class "Default")
      (node (ref "H18") (pin "1") (pinfunction "1_1") (pintype "unspecified"))
      (node (ref "R26") (pin "1") (pinfunction "1_1") (pintype "input"))
    )
    (net (code "37") (name "Net-(LED1-A)") (class "Default")
      (node (ref "LED1") (pin "1") (pinfunction "A_1") (pintype "unspecified"))
      (node (ref "R16") (pin "1") (pinfunction "1_1") (pintype "unspecified"))
    )
    (net (code "38") (name "Net-(LED2-K)") (class "Default")
      (node (ref "LED2") (pin "2") (pinfunction "K_2") (pintype "unspecified"))
      (node (ref "U19") (pin "1") (pinfunction "1_1") (pintype "unspecified"))
    )
    (net (code "39") (name "Net-(LED3-K)") (class "Default")
      (node (ref "LED3") (pin "2") (pinfunction "K_2") (pintype "unspecified"))
      (node (ref "R35") (pin "1") (pinfunction "1_1") (pintype "input"))
    )
    (net (code "40") (name "Net-(LED4-A)") (class "Default")
      (node (ref "LED4") (pin "1") (pinfunction "A_1") (pintype "unspecified"))
      (node (ref "R25") (pin "2") (pinfunction "2_2") (pintype "input"))
    )
    (net (code "41") (name "Net-(R21-Pad2)") (class "Default")
      (node (ref "R21") (pin "2") (pinfunction "2_2") (pintype "input"))
      (node (ref "R22") (pin "2") (pinfunction "2_2") (pintype "input"))
    )
    (net (code "42") (name "Net-(U15-+)") (class "Default")
      (node (ref "SW1") (pin "2") (pinfunction "2_2") (pintype "input"))
      (node (ref "U15") (pin "2") (pinfunction "+_2") (pintype "unspecified"))
    )
    (net (code "43") (name "Net-(U16-BOOT)") (class "Default")
      (node (ref "C8") (pin "2") (pinfunction "2_2") (pintype "unspecified"))
      (node (ref "U16") (pin "1") (pinfunction "BOOT_1") (pintype "unspecified"))
    )
    (net (code "44") (name "Net-(U16-COMP)") (class "Default")
      (node (ref "C10") (pin "2") (pinfunction "2_2") (pintype "input"))
      (node (ref "C9") (pin "2") (pinfunction "2_2") (pintype "input"))
      (node (ref "U16") (pin "6") (pinfunction "COMP_6") (pintype "unspecified"))
    )
    (net (code "45") (name "Net-(U16-EN)") (class "Default")
      (node (ref "R11") (pin "1") (pinfunction "1_1") (pintype "unspecified"))
      (node (ref "R12") (pin "2") (pinfunction "2_2") (pintype "unspecified"))
      (node (ref "U16") (pin "3") (pinfunction "EN_3") (pintype "unspecified"))
    )
    (net (code "46") (name "Net-(U16-SS)") (class "Default")
      (node (ref "C30") (pin "2") (pinfunction "2_2") (pintype "input"))
      (node (ref "U16") (pin "4") (pinfunction "SS_4") (pintype "unspecified"))
    )
    (net (code "47") (name "Net-(U16-VSENSE)") (class "Default")
      (node (ref "R14") (pin "1") (pinfunction "1_1") (pintype "input"))
      (node (ref "R15") (pin "1") (pinfunction "1_1") (pintype "unspecified"))
      (node (ref "U16") (pin "5") (pinfunction "VSENSE_5") (pintype "unspecified"))
    )
    (net (code "48") (name "Net-(U17-BOOT)") (class "Default")
      (node (ref "C16") (pin "2") (pinfunction "2_2") (pintype "unspecified"))
      (node (ref "U17") (pin "1") (pinfunction "BOOT_1") (pintype "unspecified"))
    )
    (net (code "49") (name "Net-(U17-COMP)") (class "Default")
      (node (ref "C17") (pin "2") (pinfunction "2_2") (pintype "input"))
      (node (ref "C18") (pin "2") (pinfunction "2_2") (pintype "input"))
      (node (ref "U17") (pin "6") (pinfunction "COMP_6") (pintype "unspecified"))
    )
    (net (code "50") (name "Net-(U17-EN)") (class "Default")
      (node (ref "R18") (pin "1") (pinfunction "1_1") (pintype "unspecified"))
      (node (ref "R19") (pin "2") (pinfunction "2_2") (pintype "unspecified"))
      (node (ref "U17") (pin "3") (pinfunction "EN_3") (pintype "unspecified"))
    )
    (net (code "51") (name "Net-(U17-SS)") (class "Default")
      (node (ref "C28") (pin "2") (pinfunction "2_2") (pintype "input"))
      (node (ref "U17") (pin "4") (pinfunction "SS_4") (pintype "unspecified"))
    )
    (net (code "52") (name "Net-(U17-VSENSE)") (class "Default")
      (node (ref "R22") (pin "1") (pinfunction "1_1") (pintype "input"))
      (node (ref "R40") (pin "1") (pinfunction "1_1") (pintype "input"))
      (node (ref "U17") (pin "5") (pinfunction "VSENSE_5") (pintype "unspecified"))
    )
    (net (code "53") (name "Net-(U18-BOOT)") (class "Default")
      (node (ref "C23") (pin "2") (pinfunction "2_2") (pintype "unspecified"))
      (node (ref "U18") (pin "1") (pinfunction "BOOT_1") (pintype "unspecified"))
    )
    (net (code "54") (name "Net-(U18-COMP)") (class "Default")
      (node (ref "C24") (pin "2") (pinfunction "2_2") (pintype "input"))
      (node (ref "C25") (pin "2") (pinfunction "2_2") (pintype "input"))
      (node (ref "U18") (pin "6") (pinfunction "COMP_6") (pintype "unspecified"))
    )
    (net (code "55") (name "Net-(U18-EN)") (class "Default")
      (node (ref "R27") (pin "1") (pinfunction "1_1") (pintype "unspecified"))
      (node (ref "R28") (pin "2") (pinfunction "2_2") (pintype "unspecified"))
      (node (ref "U18") (pin "3") (pinfunction "EN_3") (pintype "unspecified"))
    )
    (net (code "56") (name "Net-(U18-SS)") (class "Default")
      (node (ref "C29") (pin "2") (pinfunction "2_2") (pintype "input"))
      (node (ref "U18") (pin "4") (pinfunction "SS_4") (pintype "unspecified"))
    )
    (net (code "57") (name "Net-(U18-VSENSE)") (class "Default")
      (node (ref "R34") (pin "1") (pinfunction "1_1") (pintype "unspecified"))
      (node (ref "R41") (pin "1") (pinfunction "1_1") (pintype "unspecified"))
      (node (ref "U18") (pin "5") (pinfunction "VSENSE_5") (pintype "unspecified"))
    )
    (net (code "58") (name "VADJ") (class "Default")
      (node (ref "C12") (pin "1") (pinfunction "1_1") (pintype "unspecified"))
      (node (ref "C31") (pin "1") (pinfunction "1_1") (pintype "input"))
      (node (ref "H17") (pin "2") (pinfunction "2_2") (pintype "unspecified"))
      (node (ref "H3") (pin "2") (pinfunction "2_2") (pintype "unspecified"))
      (node (ref "H4") (pin "2") (pinfunction "2_2") (pintype "unspecified"))
      (node (ref "L1") (pin "2") (pinfunction "2_2") (pintype "unspecified"))
      (node (ref "R14") (pin "2") (pinfunction "2_2") (pintype "input"))
      (node (ref "R16") (pin "2") (pinfunction "2_2") (pintype "unspecified"))
    )
    (net (code "59") (name "VCC5V") (class "Default")
      (node (ref "C20") (pin "1") (pinfunction "1_1") (pintype "unspecified"))
      (node (ref "C3") (pin "1") (pinfunction "1_1") (pintype "input"))
      (node (ref "C32") (pin "1") (pinfunction "1_1") (pintype "input"))
      (node (ref "H14") (pin "1") (pinfunction "1_1") (pintype "unspecified"))
      (node (ref "H14") (pin "3") (pinfunction "3_3") (pintype "unspecified"))
      (node (ref "H14") (pin "5") (pinfunction "5_5") (pintype "unspecified"))
      (node (ref "H14") (pin "7") (pinfunction "7_7") (pintype "unspecified"))
      (node (ref "H18") (pin "3") (pinfunction "3_3") (pintype "unspecified"))
      (node (ref "H19") (pin "30") (pinfunction "30_30") (pintype "unspecified"))
      (node (ref "L2") (pin "2") (pinfunction "2_2") (pintype "unspecified"))
      (node (ref "R21") (pin "1") (pinfunction "1_1") (pintype "input"))
      (node (ref "R25") (pin "1") (pinfunction "1_1") (pintype "input"))
      (node (ref "U14") (pin "3") (pinfunction "VIN_3") (pintype "input"))
    )
    (net (code "60") (name "VCC7.2V") (class "Default")
      (node (ref "C27") (pin "1") (pinfunction "1_1") (pintype "unspecified"))
      (node (ref "C33") (pin "1") (pinfunction "1_1") (pintype "input"))
      (node (ref "CN1") (pin "2") (pinfunction "2_2") (pintype "unspecified"))
      (node (ref "L3") (pin "2") (pinfunction "2_2") (pintype "unspecified"))
      (node (ref "LED3") (pin "1") (pinfunction "A_1") (pintype "unspecified"))
      (node (ref "R41") (pin "2") (pinfunction "2_2") (pintype "unspecified"))
    )
    (net (code "61") (name "unconnected-(D7-NC-Pad2)") (class "Default")
      (node (ref "D7") (pin "2") (pinfunction "NC_2") (pintype "unspecified"))
    )
    (net (code "62") (name "unconnected-(H1-Pad1)") (class "Default")
      (node (ref "H1") (pin "1") (pinfunction "1_1") (pintype "unspecified+no_connect"))
    )
    (net (code "63") (name "unconnected-(H1-Pad2)") (class "Default")
      (node (ref "H1") (pin "2") (pinfunction "2_2") (pintype "unspecified+no_connect"))
    )
    (net (code "64") (name "unconnected-(H2-Pad1)") (class "Default")
      (node (ref "H2") (pin "1") (pinfunction "1_1") (pintype "unspecified+no_connect"))
    )
    (net (code "65") (name "unconnected-(H2-Pad2)") (class "Default")
      (node (ref "H2") (pin "2") (pinfunction "2_2") (pintype "unspecified+no_connect"))
    )
    (net (code "66") (name "unconnected-(H19-Pad12)") (class "Default")
      (node (ref "H19") (pin "12") (pinfunction "12_12") (pintype "unspecified+no_connect"))
    )
    (net (code "67") (name "unconnected-(H19-Pad14)") (class "Default")
      (node (ref "H19") (pin "14") (pinfunction "14_14") (pintype "unspecified+no_connect"))
    )
    (net (code "68") (name "unconnected-(H19-Pad16)") (class "Default")
      (node (ref "H19") (pin "16") (pinfunction "16_16") (pintype "unspecified+no_connect"))
    )
    (net (code "69") (name "unconnected-(H19-Pad18)") (class "Default")
      (node (ref "H19") (pin "18") (pinfunction "18_18") (pintype "unspecified+no_connect"))
    )
    (net (code "70") (name "unconnected-(H19-Pad22)") (class "Default")
      (node (ref "H19") (pin "22") (pinfunction "22_22") (pintype "unspecified+no_connect"))
    )
    (net (code "71") (name "unconnected-(H19-Pad24)") (class "Default")
      (node (ref "H19") (pin "24") (pinfunction "24_24") (pintype "unspecified+no_connect"))
    )
    (net (code "72") (name "unconnected-(H19-Pad26)") (class "Default")
      (node (ref "H19") (pin "26") (pinfunction "26_26") (pintype "unspecified+no_connect"))
    )
    (net (code "73") (name "unconnected-(H19-Pad28)") (class "Default")
      (node (ref "H19") (pin "28") (pinfunction "28_28") (pintype "unspecified+no_connect"))
    )
    (net (code "74") (name "unconnected-(R15-Pad3)") (class "Default")
      (node (ref "R15") (pin "3") (pinfunction "3_3") (pintype "unspecified+no_connect"))
    )
    (net (code "75") (name "unconnected-(R34-Pad3)") (class "Default")
      (node (ref "R34") (pin "3") (pinfunction "3_3") (pintype "unspecified+no_connect"))
    )
  )
)
